# 1XGSH00_BATTERY.net
KiCad netlist of a schematic drawn in Altium Designer
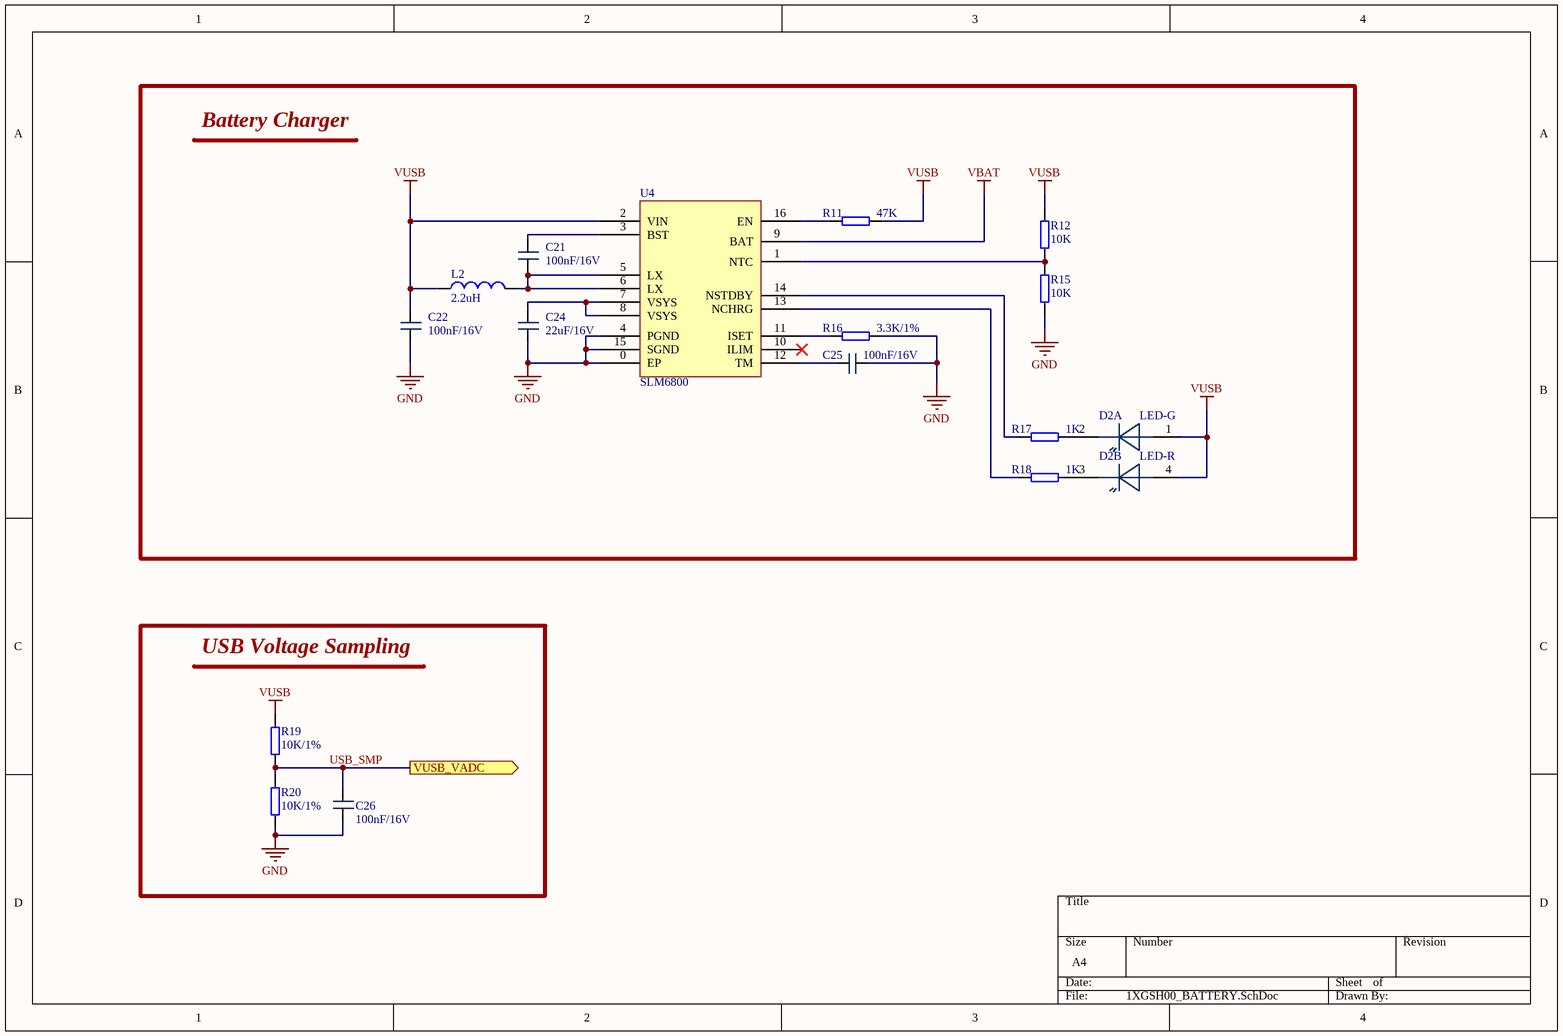
[diagram p0: 1XGSH00_BATTERY.SchDoc]

(export (version "E")
  (design (tool "Eeschema 10.0.6"))
  (components
    (comp (ref "C21")
      (value "100nF/16V")
      (footprint "0805_C")
      (description "Capacitor")
      (libsource (lib "LGG21") (part "Capacitor"))
    )
    (comp (ref "C22")
      (value "100nF/16V")
      (footprint "0603_C")
      (description "Capacitor")
      (libsource (lib "LGG21") (part "Capacitor"))
    )
    (comp (ref "C24")
      (value "22uF/16V")
      (footprint "0805_C")
      (description "Capacitor")
      (libsource (lib "LGG21") (part "Capacitor"))
    )
    (comp (ref "C25")
      (value "100nF/16V")
      (footprint "0805_C")
      (description "Capacitor")
      (libsource (lib "LGG21") (part "Capacitor"))
    )
    (comp (ref "C26")
      (value "100nF/16V")
      (footprint "0402_C")
      (description "Capacitor")
      (libsource (lib "LGG21") (part "Capacitor"))
    )
    (comp (ref "D2")
      (value "LED-R")
      (footprint "3528_LED")
      (description "Dual LED Single Package")
      (libsource (lib "LGG21") (part "LED_Dual_2"))
    )
    (comp (ref "L2")
      (value "2.2uH")
      (footprint "INDUCTOR_4*4")
      (description "Inductor")
      (fields (field (name "PUBLISHER") "Altium Limited"))
      (libsource (lib "LGG21") (part "Inductor"))
    )
    (comp (ref "R11")
      (value "47K")
      (footprint "0402_R")
      (description "Resistor")
      (libsource (lib "LGG21") (part "Resistor"))
    )
    (comp (ref "R12")
      (value "10K")
      (footprint "0402_R")
      (description "Resistor")
      (libsource (lib "LGG21") (part "Resistor"))
    )
    (comp (ref "R15")
      (value "10K")
      (footprint "0402_R")
      (description "Resistor")
      (libsource (lib "LGG21") (part "Resistor"))
    )
    (comp (ref "R16")
      (value "3.3K/1%")
      (footprint "0402_R")
      (description "Resistor")
      (libsource (lib "LGG21") (part "Resistor"))
    )
    (comp (ref "R17")
      (value "1K")
      (footprint "0402_R")
      (description "Resistor")
      (libsource (lib "LGG21") (part "Resistor"))
    )
    (comp (ref "R18")
      (value "1K")
      (footprint "0402_R")
      (description "Resistor")
      (libsource (lib "LGG21") (part "Resistor"))
    )
    (comp (ref "R19")
      (value "10K/1%")
      (footprint "0402_R")
      (description "Resistor")
      (libsource (lib "LGG21") (part "Resistor"))
    )
    (comp (ref "R20")
      (value "10K/1%")
      (footprint "0402_R")
      (description "Resistor")
      (libsource (lib "LGG21") (part "Resistor"))
    )
    (comp (ref "U4")
      (value "SLM6800")
      (footprint "QFN-16_L4.0-W4.0-P0.65-LS4.2-BL-EP")
      (description "5V 输入两节锂电池升压充电IC")
      (libsource (lib "LGG21") (part "SLM6800"))
    )
  )
  (nets
    (net (code "1") (name "/USB_SMP") (class "Default")
      (node (ref "C26") (pin "2") (pinfunction "-_2") (pintype "passive"))
      (node (ref "R19") (pin "2") (pinfunction "2_2") (pintype "passive"))
      (node (ref "R20") (pin "1") (pinfunction "1_1") (pintype "passive"))
    )
    (net (code "2") (name "GND") (class "Default")
      (node (ref "C22") (pin "1") (pinfunction "-_1") (pintype "passive"))
      (node (ref "C24") (pin "1") (pinfunction "-_1") (pintype "passive"))
      (node (ref "C25") (pin "2") (pinfunction "-_2") (pintype "passive"))
      (node (ref "C26") (pin "1") (pinfunction "-_1") (pintype "passive"))
      (node (ref "R15") (pin "2") (pinfunction "2_2") (pintype "passive"))
      (node (ref "R16") (pin "2") (pinfunction "2_2") (pintype "passive"))
      (node (ref "R20") (pin "2") (pinfunction "2_2") (pintype "passive"))
      (node (ref "U4") (pin "0") (pinfunction "EP_0") (pintype "passive"))
      (node (ref "U4") (pin "15") (pinfunction "SGND_15") (pintype "passive"))
      (node (ref "U4") (pin "4") (pinfunction "PGND_4") (pintype "passive"))
    )
    (net (code "3") (name "Net-(C21---Pad1)") (class "Default")
      (node (ref "C21") (pin "1") (pinfunction "-_1") (pintype "passive"))
      (node (ref "L2") (pin "2") (pinfunction "2_2") (pintype "passive"))
      (node (ref "U4") (pin "5") (pinfunction "LX_5") (pintype "passive"))
      (node (ref "U4") (pin "6") (pinfunction "LX_6") (pintype "passive"))
    )
    (net (code "4") (name "Net-(C24---Pad2)") (class "Default")
      (node (ref "C24") (pin "2") (pinfunction "-_2") (pintype "passive"))
      (node (ref "U4") (pin "7") (pinfunction "VSYS_7") (pintype "passive"))
      (node (ref "U4") (pin "8") (pinfunction "VSYS_8") (pintype "passive"))
    )
    (net (code "5") (name "Net-(D2A-1)") (class "Default")
      (node (ref "D2") (pin "2") (pinfunction "1_2") (pintype "passive"))
      (node (ref "R17") (pin "2") (pinfunction "2_2") (pintype "passive"))
    )
    (net (code "6") (name "Net-(D2B-2)") (class "Default")
      (node (ref "D2") (pin "3") (pinfunction "2_3") (pintype "passive"))
      (node (ref "R18") (pin "2") (pinfunction "2_2") (pintype "passive"))
    )
    (net (code "7") (name "Net-(U4-BST)") (class "Default")
      (node (ref "C21") (pin "2") (pinfunction "-_2") (pintype "passive"))
      (node (ref "U4") (pin "3") (pinfunction "BST_3") (pintype "passive"))
    )
    (net (code "8") (name "Net-(U4-EN)") (class "Default")
      (node (ref "R11") (pin "1") (pinfunction "1_1") (pintype "passive"))
      (node (ref "U4") (pin "16") (pinfunction "EN_16") (pintype "passive"))
    )
    (net (code "9") (name "Net-(U4-ISET)") (class "Default")
      (node (ref "R16") (pin "1") (pinfunction "1_1") (pintype "passive"))
      (node (ref "U4") (pin "11") (pinfunction "ISET_11") (pintype "passive"))
    )
    (net (code "10") (name "Net-(U4-NCHRG)") (class "Default")
      (node (ref "R18") (pin "1") (pinfunction "1_1") (pintype "passive"))
      (node (ref "U4") (pin "13") (pinfunction "NCHRG_13") (pintype "passive"))
    )
    (net (code "11") (name "Net-(U4-NSTDBY)") (class "Default")
      (node (ref "R17") (pin "1") (pinfunction "1_1") (pintype "passive"))
      (node (ref "U4") (pin "14") (pinfunction "NSTDBY_14") (pintype "passive"))
    )
    (net (code "12") (name "Net-(U4-NTC)") (class "Default")
      (node (ref "R12") (pin "2") (pinfunction "2_2") (pintype "passive"))
      (node (ref "R15") (pin "1") (pinfunction "1_1") (pintype "passive"))
      (node (ref "U4") (pin "1") (pinfunction "NTC_1") (pintype "passive"))
    )
    (net (code "13") (name "Net-(U4-TM)") (class "Default")
      (node (ref "C25") (pin "1") (pinfunction "-_1") (pintype "passive"))
      (node (ref "U4") (pin "12") (pinfunction "TM_12") (pintype "passive"))
    )
    (net (code "14") (name "VBAT") (class "Default")
      (node (ref "U4") (pin "9") (pinfunction "BAT_9") (pintype "passive"))
    )
    (net (code "15") (name "VUSB") (class "Default")
      (node (ref "C22") (pin "2") (pinfunction "-_2") (pintype "passive"))
      (node (ref "D2") (pin "1") (pinfunction "0_1") (pintype "passive"))
      (node (ref "D2") (pin "4") (pinfunction "3_4") (pintype "passive"))
      (node (ref "L2") (pin "1") (pinfunction "1_1") (pintype "passive"))
      (node (ref "R11") (pin "2") (pinfunction "2_2") (pintype "passive"))
      (node (ref "R12") (pin "1") (pinfunction "1_1") (pintype "passive"))
      (node (ref "R19") (pin "1") (pinfunction "1_1") (pintype "passive"))
      (node (ref "U4") (pin "2") (pinfunction "VIN_2") (pintype "passive"))
    )
    (net (code "16") (name "unconnected-(U4-ILIM-Pad10)") (class "Default")
      (node (ref "U4") (pin "10") (pinfunction "ILIM_10") (pintype "passive+no_connect"))
    )
  )
)
